# Communication.net
KiCad netlist of a schematic drawn in EAGLE
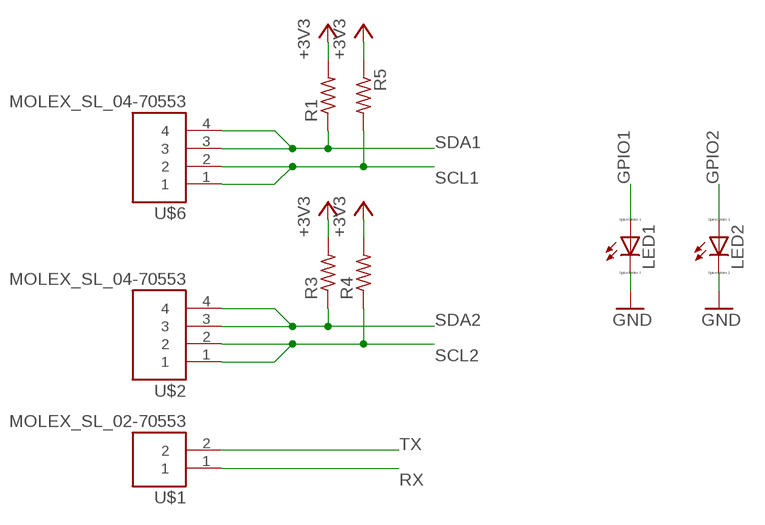
[diagram p0: schematic, sheet 1]

(export (version "E")
  (design (tool "Eeschema 10.0.6"))
  (components
    (comp (ref "LED1")
      (value "LED_E")
      (footprint "eagle-import:LED_1206")
      (libsource (lib "eagle-import") (part "LED_E"))
    )
    (comp (ref "LED2")
      (value "LED_E")
      (footprint "eagle-import:LED_1206")
      (libsource (lib "eagle-import") (part "LED_E"))
    )
    (comp (ref "R1")
      (value "R-US_M1206")
      (footprint "eagle-import:M1206")
      (libsource (lib "eagle-import") (part "R-US_M1206"))
    )
    (comp (ref "R3")
      (value "R-US_M1206")
      (footprint "eagle-import:M1206")
      (libsource (lib "eagle-import") (part "R-US_M1206"))
    )
    (comp (ref "R4")
      (value "R-US_M1206")
      (footprint "eagle-import:M1206")
      (libsource (lib "eagle-import") (part "R-US_M1206"))
    )
    (comp (ref "R5")
      (value "R-US_M1206")
      (footprint "eagle-import:M1206")
      (libsource (lib "eagle-import") (part "R-US_M1206"))
    )
    (comp (ref "U$1")
      (value "MOLEX_SL_02-70553")
      (footprint "eagle-import:SL_70553_2")
      (libsource (lib "eagle-import") (part "MOLEX_SL_02-70553"))
    )
    (comp (ref "U$2")
      (value "MOLEX_SL_04-70553")
      (footprint "eagle-import:SL_70553_4")
      (libsource (lib "eagle-import") (part "MOLEX_SL_04-70553"))
    )
    (comp (ref "U$6")
      (value "MOLEX_SL_04-70553")
      (footprint "eagle-import:SL_70553_4")
      (libsource (lib "eagle-import") (part "MOLEX_SL_04-70553"))
    )
  )
  (nets
    (net (code "1") (name "+3V3") (class "Default")
      (node (ref "R1") (pin "2") (pinfunction "2_2") (pintype "passive"))
      (node (ref "R3") (pin "2") (pinfunction "2_2") (pintype "passive"))
      (node (ref "R4") (pin "2") (pinfunction "2_2") (pintype "passive"))
      (node (ref "R5") (pin "1") (pinfunction "1_1") (pintype "passive"))
    )
    (net (code "2") (name "/GPIO1") (class "Default")
      (node (ref "LED1") (pin "A") (pinfunction "A_A") (pintype "passive"))
    )
    (net (code "3") (name "/GPIO2") (class "Default")
      (node (ref "LED2") (pin "A") (pinfunction "A_A") (pintype "passive"))
    )
    (net (code "4") (name "/RX") (class "Default")
      (node (ref "U$1") (pin "1") (pinfunction "1_1") (pintype "bidirectional"))
    )
    (net (code "5") (name "/SCL1") (class "Default")
      (node (ref "R5") (pin "2") (pinfunction "2_2") (pintype "passive"))
      (node (ref "U$6") (pin "1") (pinfunction "1_1") (pintype "bidirectional"))
      (node (ref "U$6") (pin "2") (pinfunction "2_2") (pintype "bidirectional"))
    )
    (net (code "6") (name "/SCL2") (class "Default")
      (node (ref "R4") (pin "1") (pinfunction "1_1") (pintype "passive"))
      (node (ref "U$2") (pin "1") (pinfunction "1_1") (pintype "bidirectional"))
      (node (ref "U$2") (pin "2") (pinfunction "2_2") (pintype "bidirectional"))
    )
    (net (code "7") (name "/SDA1") (class "Default")
      (node (ref "R1") (pin "1") (pinfunction "1_1") (pintype "passive"))
      (node (ref "U$6") (pin "3") (pinfunction "3_3") (pintype "bidirectional"))
      (node (ref "U$6") (pin "4") (pinfunction "4_4") (pintype "bidirectional"))
    )
    (net (code "8") (name "/SDA2") (class "Default")
      (node (ref "R3") (pin "1") (pinfunction "1_1") (pintype "passive"))
      (node (ref "U$2") (pin "3") (pinfunction "3_3") (pintype "bidirectional"))
      (node (ref "U$2") (pin "4") (pinfunction "4_4") (pintype "bidirectional"))
    )
    (net (code "9") (name "/TX") (class "Default")
      (node (ref "U$1") (pin "2") (pinfunction "2_2") (pintype "bidirectional"))
    )
    (net (code "10") (name "GND") (class "Default")
      (node (ref "LED1") (pin "C") (pinfunction "C_C") (pintype "passive"))
      (node (ref "LED2") (pin "C") (pinfunction "C_C") (pintype "passive"))
    )
  )
)
